# USB_Host.net
KiCad netlist of a schematic drawn in Altium Designer
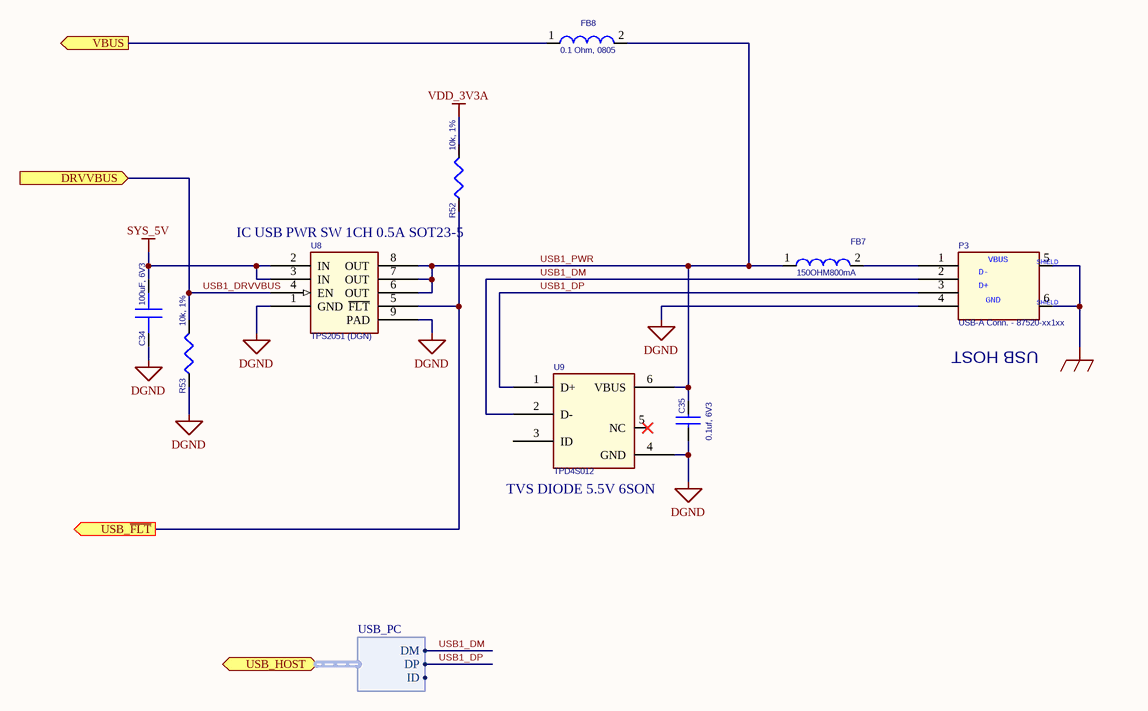
[diagram p0: USB_Host.SchDoc]

(export (version "E")
  (design (tool "Eeschema 10.0.6"))
  (components
    (comp (ref "C34")
      (value "100uF, 6V3")
      (footprint "RD205SMD_250D")
      (description "CAP ALUM 100UF 6.3V 20% SMD")
      (fields
        (field (name "MANUFACTURER") "Cornell Dubilier Electronics (CDE)")
        (field (name "MANUFACTURER PART NUMBER") "AVE107M06D16T-F")
      )
      (libsource (lib "BEAGLEBONEBLACK_REV A5B") (part "CAP SMD"))
    )
    (comp (ref "C35")
      (value "0.1uf, 6V3")
      (footprint "402")
      (description "CAP CER 0.1UF 6.3V 10% X5R 0402")
      (fields
        (field (name "MANUFACTURER") "TDK Corporation")
        (field (name "MANUFACTURER PART NUMBER") "C1005X5R0J104K050BA")
      )
      (libsource (lib "BEAGLEBONEBLACK_REV A5B") (part "CAP_0.1uF_X7R_16V_10% 0402"))
    )
    (comp (ref "FB7")
      (value "150OHM800mA")
      (footprint "SM-7351-IND-0805")
      (description "FERRITE 800MA 150 OHM 0805 SMD")
      (fields (field (name "MFR") "Steward") (field (name "TIINTPARTNUMBER") "1L0010"))
      (libsource (lib "BEAGLEBONEBLACK_REV A5B") (part "FER_180_200_0"))
    )
    (comp (ref "FB8")
      (value "0.1 Ohm, 0805")
      (footprint "SM-7351-IND-0805")
      (description "RES .10 OHM 1/8W 5% 0805")
      (fields
        (field (name "MANUFACTURER") "CTS Resistor Products")
        (field (name "MANUFACTURER PART NUMBER") "73L3R10J")
      )
      (libsource (lib "BEAGLEBONEBLACK_REV A5B") (part "FER_180_200_0"))
    )
    (comp (ref "P3")
      (value "USB-A Conn. - 87520-xx1xx")
      (description "CONN RCPT USB TYPE A R/A PCB")
      (fields (field (name "MANUFACTURER") "FCI") (field (name "MANUFACTURER PART NUMBER") "87520-0010BLF"))
      (libsource (lib "BEAGLEBONEBLACK_REV A5B") (part "CONN_54819-0578_2"))
    )
    (comp (ref "R52")
      (value "10k, 1%")
      (footprint "402")
      (description "RES 10K OHM 1/16W 5% 0402 SMD")
      (fields
        (field (name "MANUFACTURER") "Rohm Semiconductor")
        (field (name "MANUFACTURER PART NUMBER") "MCR01MZPJ103")
      )
      (libsource (lib "BEAGLEBONEBLACK_REV A5B") (part "RES SMD"))
    )
    (comp (ref "R53")
      (value "10k, 1%")
      (footprint "402")
      (description "RES 10K OHM 1/16W 5% 0402 SMD")
      (fields
        (field (name "MANUFACTURER") "Rohm Semiconductor")
        (field (name "MANUFACTURER PART NUMBER") "MCR01MZPJ103")
      )
      (libsource (lib "BEAGLEBONEBLACK_REV A5B") (part "RES SMD"))
    )
    (comp (ref "U8")
      (value "TPS2051 (DGN)")
      (description "IC 1.5A PWR DIST SWITCH 8-SOIC")
      (fields
        (field (name "MANUFACTURER") "Texas Instruments")
        (field (name "MANUFACTURER PART NUMBER") "TPS2051BDGNR")
      )
      (libsource (lib "BEAGLEBONEBLACK_REV A5B") (part "TPS2061_0"))
    )
    (comp (ref "U9")
      (value "TPD4S012")
      (footprint "U_6_DRY")
      (description "ESD 4channel USB Interface")
      (fields (field (name "MFR") "TI") (field (name "TIINTPARTNUMBER") "1A0233"))
      (libsource (lib "BEAGLEBONEBLACK_REV A5B") (part "PROT_TPD4S012"))
    )
  )
  (nets
    (net (code "2") (name "/USB1_DM") (class "Default")
      (node (ref "P3") (pin "2") (pinfunction "P2_2") (pintype "passive"))
      (node (ref "U9") (pin "2") (pinfunction "D-_2") (pintype "passive"))
    )
    (net (code "3") (name "/USB1_DP") (class "Default")
      (node (ref "P3") (pin "3") (pinfunction "P3_3") (pintype "passive"))
      (node (ref "U9") (pin "1") (pinfunction "D+_1") (pintype "passive"))
    )
    (net (code "4") (name "/USB1_DRVVBUS") (class "Default")
      (node (ref "R53") (pin "1") (pinfunction "P1_1") (pintype "passive"))
      (node (ref "U8") (pin "4") (pinfunction "EN_4") (pintype "input"))
    )
    (net (code "5") (name "/USB1_PWR") (class "Default")
      (node (ref "C35") (pin "1") (pinfunction "1_1") (pintype "passive"))
      (node (ref "FB7") (pin "1") (pinfunction "1_1") (pintype "passive"))
      (node (ref "FB8") (pin "2") (pinfunction "2_2") (pintype "passive"))
      (node (ref "U8") (pin "6") (pinfunction "OUT_6") (pintype "power_in"))
      (node (ref "U8") (pin "7") (pinfunction "OUT_7") (pintype "power_in"))
      (node (ref "U8") (pin "8") (pinfunction "OUT_8") (pintype "power_in"))
      (node (ref "U9") (pin "6") (pinfunction "VBUS_6") (pintype "power_in"))
    )
    (net (code "6") (name "/USB_~{FLT}") (class "Default")
      (node (ref "R52") (pin "2") (pinfunction "P2_2") (pintype "passive"))
      (node (ref "U8") (pin "5") (pinfunction "~{FLT}_5") (pintype "open_collector"))
    )
    (net (code "7") (name "/VBUS") (class "Default")
      (node (ref "FB8") (pin "1") (pinfunction "1_1") (pintype "passive"))
    )
    (net (code "9") (name "DGND") (class "Default")
      (node (ref "C34") (pin "2") (pinfunction "2_2") (pintype "passive"))
      (node (ref "C35") (pin "2") (pinfunction "2_2") (pintype "passive"))
      (node (ref "P3") (pin "4") (pinfunction "P4_4") (pintype "passive"))
      (node (ref "R53") (pin "2") (pinfunction "P2_2") (pintype "passive"))
      (node (ref "U8") (pin "1") (pinfunction "GND_1") (pintype "power_in"))
      (node (ref "U8") (pin "9") (pinfunction "PAD_9") (pintype "passive"))
      (node (ref "U9") (pin "4") (pinfunction "GND_4") (pintype "power_in"))
    )
    (net (code "10") (name "GND_EARTH") (class "Default")
      (node (ref "P3") (pin "5") (pinfunction "SHELD1_5") (pintype "passive"))
      (node (ref "P3") (pin "6") (pinfunction "PAD4_6") (pintype "passive"))
    )
    (net (code "11") (name "Net-(P3-P1)") (class "Default")
      (node (ref "FB7") (pin "2") (pinfunction "2_2") (pintype "passive"))
      (node (ref "P3") (pin "1") (pinfunction "P1_1") (pintype "passive"))
    )
    (net (code "12") (name "SYS_5V") (class "Default")
      (node (ref "C34") (pin "1") (pinfunction "1_1") (pintype "passive"))
      (node (ref "U8") (pin "2") (pinfunction "IN_2") (pintype "power_in"))
      (node (ref "U8") (pin "3") (pinfunction "IN_3") (pintype "power_in"))
    )
    (net (code "13") (name "VDD_3V3A") (class "Default")
      (node (ref "R52") (pin "1") (pinfunction "P1_1") (pintype "passive"))
    )
    (net (code "14") (name "unconnected-(U9-ID-Pad3)") (class "Default")
      (node (ref "U9") (pin "3") (pinfunction "ID_3") (pintype "passive"))
    )
    (net (code "15") (name "unconnected-(U9-NC-Pad5)") (class "Default")
      (node (ref "U9") (pin "5") (pinfunction "NC_5") (pintype "passive+no_connect"))
    )
  )
)
